# QuadV3.net
KiCad netlist of a schematic drawn in EasyEDA
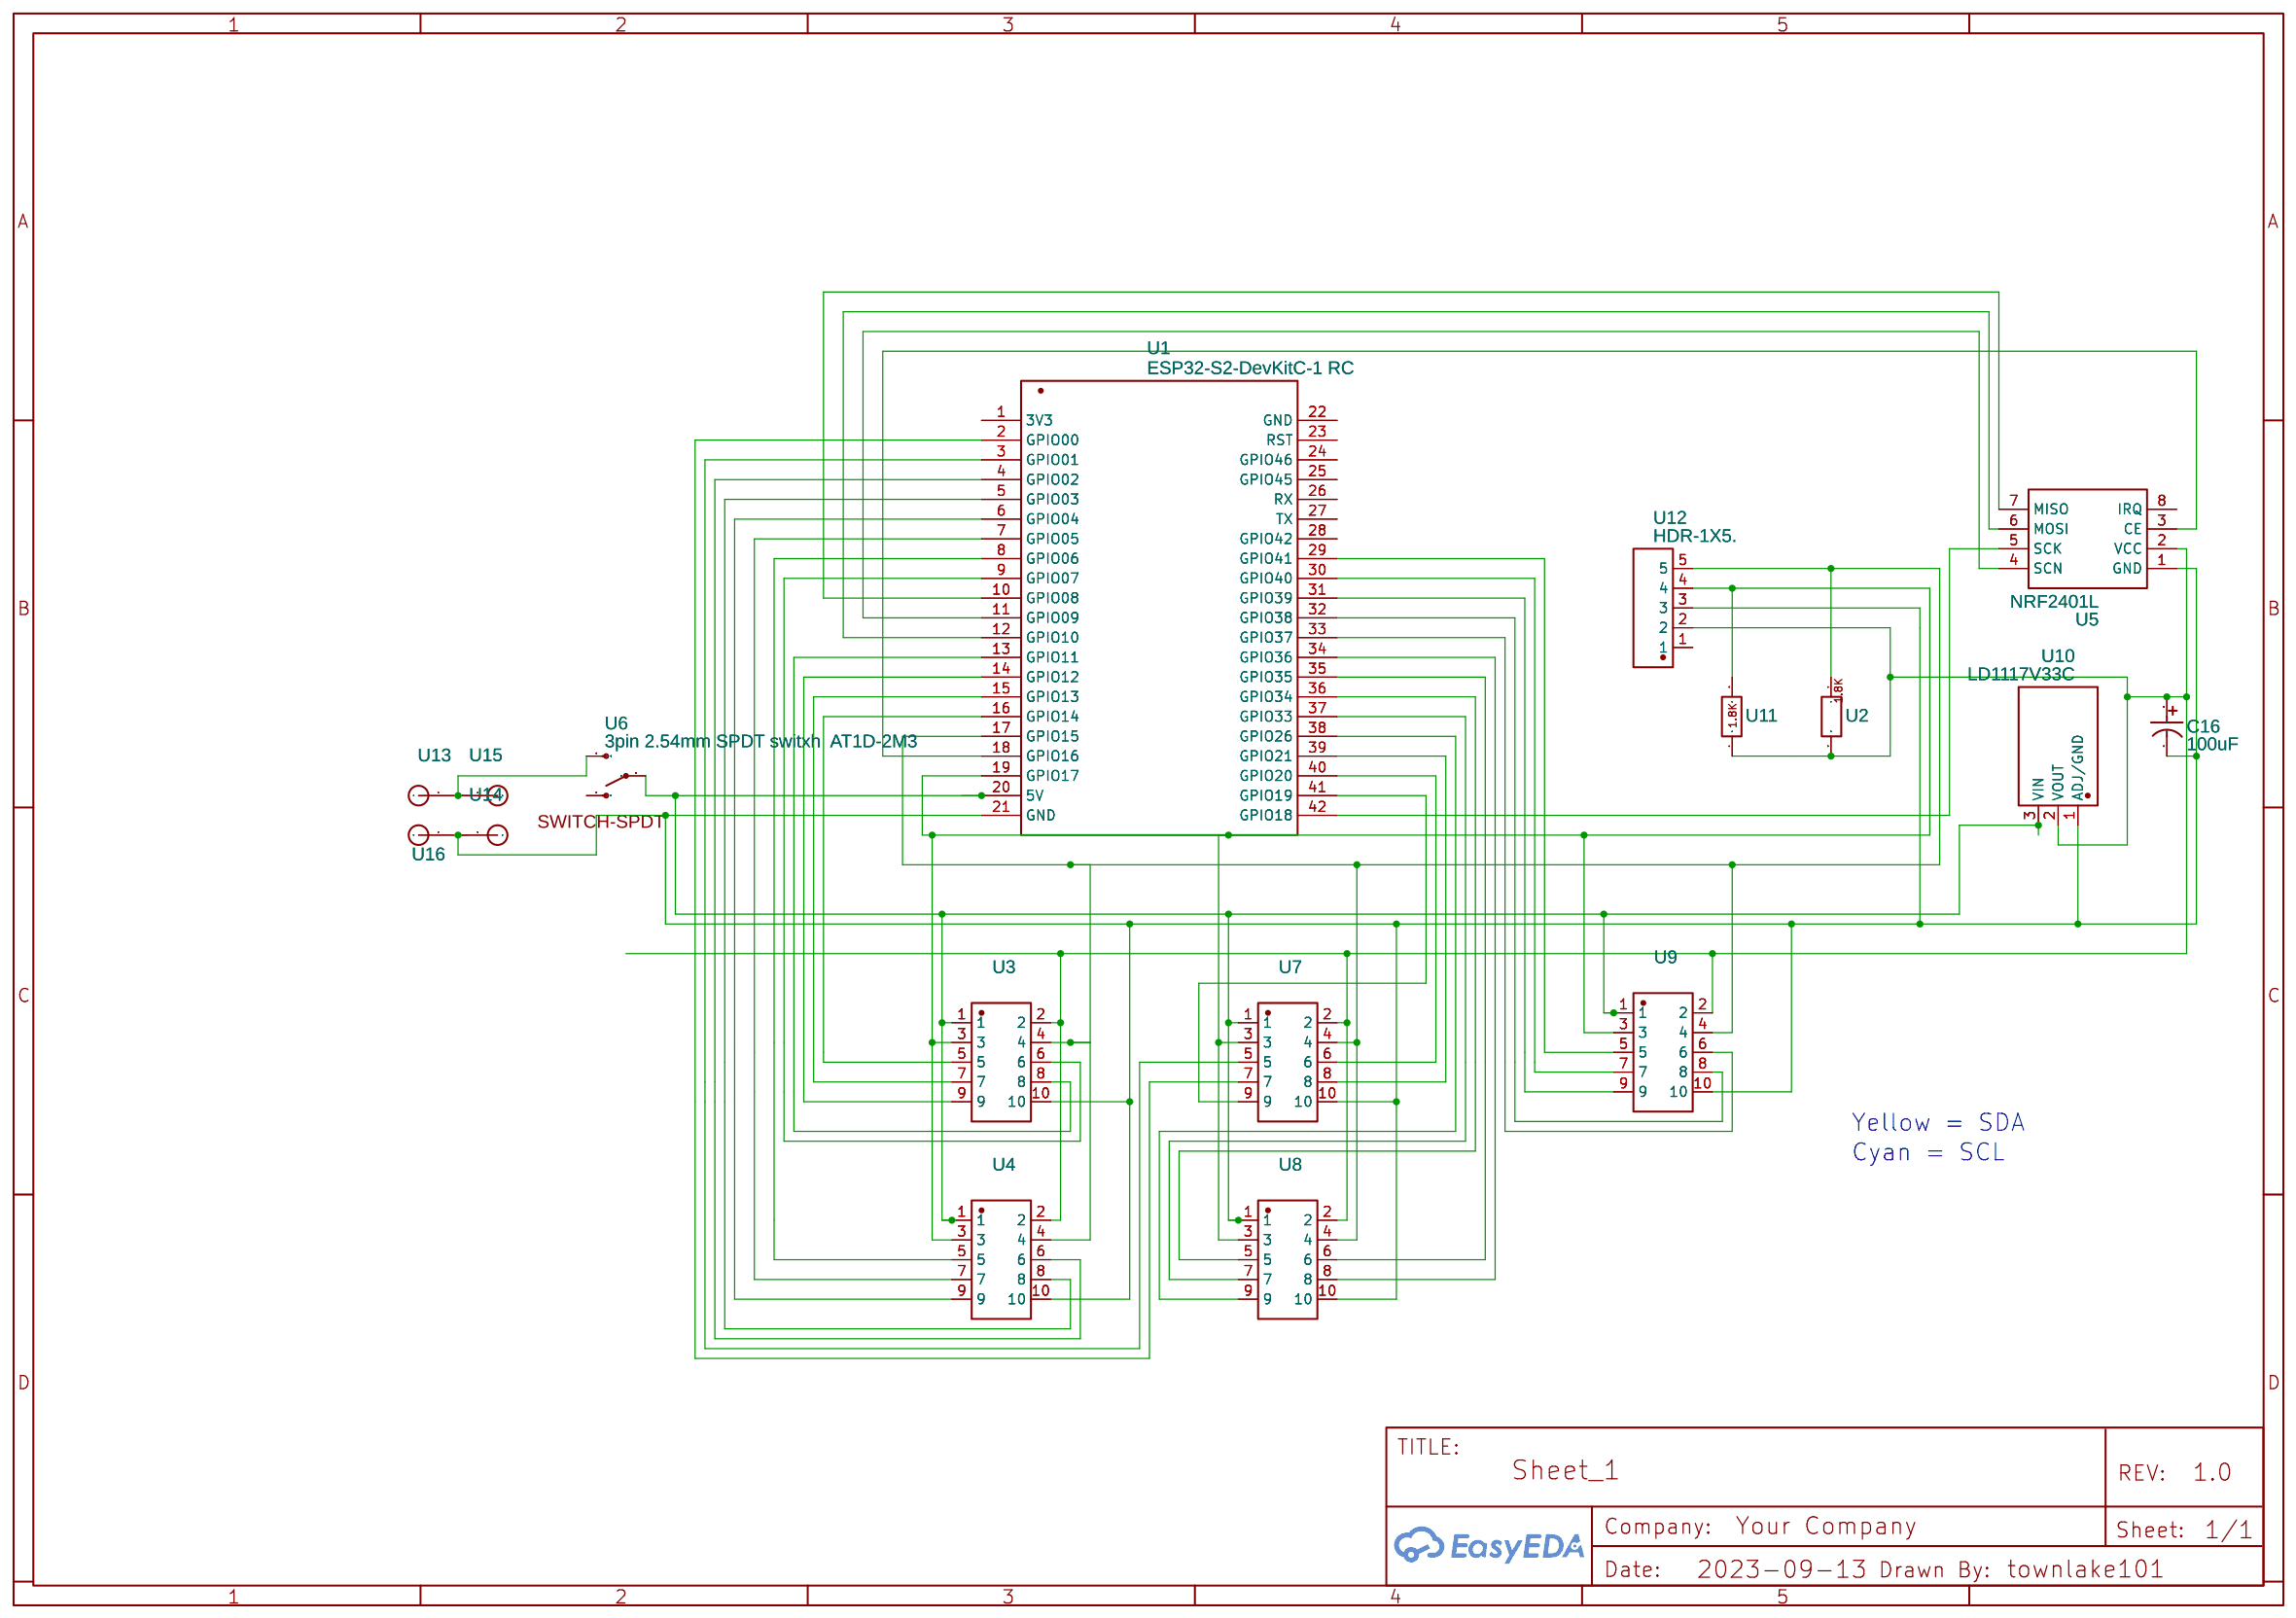
[diagram p0: schematic sheet]

(export (version "E")
  (design (tool "Eeschema 10.0.6"))
  (components
    (comp (ref "C16")
      (value "100uF")
      (fields (field (name "Manufacturer Part") "Jweo"))
      (libsource (lib "") (part "CAP-POL-1"))
    )
    (comp (ref "U1")
      (value "ESP32-S2-DevKitC-1 RC")
      (fields
        (field (name "Manufacturer Part") "ESP32-S2-DevKitC-1")
        (field (name "Manufacturer") "Espressif Manifacturer")
      )
      (libsource (lib "") (part "ESP32-S2-DevKitC-1 RC"))
    )
    (comp (ref "U2") (value "NO") (libsource (lib "") (part "1.8K_R_1/2W")))
    (comp (ref "U3")
      (value "NO")
      (fields
        (field (name "Manufacturer Part") "KH-2.54PH180-2X5P-L8.9")
        (field (name "Manufacturer") "kinghelm(金航标)")
      )
      (libsource (lib "") (part "KH-2.54PH180-2X5P"))
    )
    (comp (ref "U4")
      (value "NO")
      (fields
        (field (name "Manufacturer Part") "KH-2.54PH180-2X5P-L8.9")
        (field (name "Manufacturer") "kinghelm(金航标)")
      )
      (libsource (lib "") (part "KH-2.54PH180-2X5P"))
    )
    (comp (ref "U5")
      (value "NRF2401L")
      (fields (field (name "Manufacturer Part") "nrf2401l"))
      (libsource (lib "") (part "NRF2401L"))
    )
    (comp (ref "U6")
      (value "3pin 2.54mm SPDT switxh  AT1D-2M3")
      (libsource (lib "") (part "3pin 2.54mm SPDT switxh  AT1D-2M3"))
    )
    (comp (ref "U7")
      (value "NO")
      (fields
        (field (name "Manufacturer Part") "KH-2.54PH180-2X5P-L8.9")
        (field (name "Manufacturer") "kinghelm(金航标)")
      )
      (libsource (lib "") (part "KH-2.54PH180-2X5P"))
    )
    (comp (ref "U8")
      (value "NO")
      (fields
        (field (name "Manufacturer Part") "KH-2.54PH180-2X5P-L8.9")
        (field (name "Manufacturer") "kinghelm(金航标)")
      )
      (libsource (lib "") (part "KH-2.54PH180-2X5P"))
    )
    (comp (ref "U9")
      (value "NO")
      (fields
        (field (name "Manufacturer Part") "KH-2.54PH180-2X5P-L8.9")
        (field (name "Manufacturer") "kinghelm(金航标)")
      )
      (libsource (lib "") (part "KH-2.54PH180-2X5P"))
    )
    (comp (ref "U10")
      (value "LD1117V33C")
      (fields (field (name "Manufacturer") "ST(意法半导体)"))
      (libsource (lib "") (part "LD1117V33C"))
    )
    (comp (ref "U11") (value "NO") (libsource (lib "") (part "1.8K_R_1/2W_1")))
    (comp (ref "U12")
      (value "HDR-1X5.")
      (fields (field (name "Manufacturer Part") "HDR-1X5插件"))
      (libsource (lib "") (part "HDR-1X5."))
    )
    (comp (ref "U13")
      (value "NO")
      (fields (field (name "Manufacturer Part") "Wire Hole"))
      (libsource (lib "") (part "Wire Hole 14AWG"))
    )
    (comp (ref "U14")
      (value "NO")
      (fields (field (name "Manufacturer Part") "Wire Hole"))
      (libsource (lib "") (part "Wire Hole 14AWG_1"))
    )
    (comp (ref "U15")
      (value "NO")
      (fields (field (name "Manufacturer Part") "Wire Hole"))
      (libsource (lib "") (part "Wire Hole 14AWG_1"))
    )
    (comp (ref "U16")
      (value "NO")
      (fields (field (name "Manufacturer Part") "Wire Hole"))
      (libsource (lib "") (part "Wire Hole 14AWG"))
    )
  )
  (nets
    (net (code "1") (name "Net-(U1-5V)") (class "Default")
      (node (ref "U1") (pin "20") (pinfunction "5V_20") (pintype "bidirectional"))
      (node (ref "U10") (pin "3") (pinfunction "VIN_3") (pintype "unspecified"))
      (node (ref "U3") (pin "1") (pinfunction "1_1") (pintype "unspecified"))
      (node (ref "U4") (pin "1") (pinfunction "1_1") (pintype "unspecified"))
      (node (ref "U6") (pin "2") (pinfunction "P_2") (pintype "unspecified"))
      (node (ref "U7") (pin "1") (pinfunction "1_1") (pintype "unspecified"))
      (node (ref "U8") (pin "1") (pinfunction "1_1") (pintype "unspecified"))
      (node (ref "U9") (pin "1") (pinfunction "1_1") (pintype "unspecified"))
    )
    (net (code "2") (name "Net-(U1-GPIO00)") (class "Default")
      (node (ref "U1") (pin "2") (pinfunction "GPIO00_2") (pintype "passive"))
      (node (ref "U7") (pin "7") (pinfunction "7_7") (pintype "unspecified"))
    )
    (net (code "3") (name "Net-(U1-GPIO01)") (class "Default")
      (node (ref "U1") (pin "3") (pinfunction "GPIO01_3") (pintype "bidirectional"))
      (node (ref "U7") (pin "5") (pinfunction "5_5") (pintype "unspecified"))
    )
    (net (code "4") (name "Net-(U1-GPIO02)") (class "Default")
      (node (ref "U1") (pin "4") (pinfunction "GPIO02_4") (pintype "bidirectional"))
      (node (ref "U4") (pin "6") (pinfunction "6_6") (pintype "unspecified"))
    )
    (net (code "5") (name "Net-(U1-GPIO03)") (class "Default")
      (node (ref "U1") (pin "5") (pinfunction "GPIO03_5") (pintype "bidirectional"))
      (node (ref "U4") (pin "8") (pinfunction "8_8") (pintype "unspecified"))
    )
    (net (code "6") (name "Net-(U1-GPIO04)") (class "Default")
      (node (ref "U1") (pin "6") (pinfunction "GPIO04_6") (pintype "bidirectional"))
      (node (ref "U4") (pin "9") (pinfunction "9_9") (pintype "unspecified"))
    )
    (net (code "7") (name "Net-(U1-GPIO05)") (class "Default")
      (node (ref "U1") (pin "7") (pinfunction "GPIO05_7") (pintype "bidirectional"))
      (node (ref "U4") (pin "7") (pinfunction "7_7") (pintype "unspecified"))
    )
    (net (code "8") (name "Net-(U1-GPIO06)") (class "Default")
      (node (ref "U1") (pin "8") (pinfunction "GPIO06_8") (pintype "bidirectional"))
      (node (ref "U4") (pin "5") (pinfunction "5_5") (pintype "unspecified"))
    )
    (net (code "9") (name "Net-(U1-GPIO07)") (class "Default")
      (node (ref "U1") (pin "9") (pinfunction "GPIO07_9") (pintype "bidirectional"))
      (node (ref "U3") (pin "6") (pinfunction "6_6") (pintype "unspecified"))
    )
    (net (code "10") (name "Net-(U1-GPIO08)") (class "Default")
      (node (ref "U1") (pin "10") (pinfunction "GPIO08_10") (pintype "bidirectional"))
      (node (ref "U5") (pin "7") (pinfunction "MISO_7") (pintype "unspecified"))
    )
    (net (code "11") (name "Net-(U1-GPIO09)") (class "Default")
      (node (ref "U1") (pin "11") (pinfunction "GPIO09_11") (pintype "bidirectional"))
      (node (ref "U5") (pin "4") (pinfunction "SCN_4") (pintype "unspecified"))
    )
    (net (code "12") (name "Net-(U1-GPIO10)") (class "Default")
      (node (ref "U1") (pin "12") (pinfunction "GPIO10_12") (pintype "bidirectional"))
      (node (ref "U5") (pin "6") (pinfunction "MOSI_6") (pintype "unspecified"))
    )
    (net (code "13") (name "Net-(U1-GPIO11)") (class "Default")
      (node (ref "U1") (pin "13") (pinfunction "GPIO11_13") (pintype "bidirectional"))
      (node (ref "U3") (pin "8") (pinfunction "8_8") (pintype "unspecified"))
    )
    (net (code "14") (name "Net-(U1-GPIO12)") (class "Default")
      (node (ref "U1") (pin "14") (pinfunction "GPIO12_14") (pintype "bidirectional"))
      (node (ref "U3") (pin "9") (pinfunction "9_9") (pintype "unspecified"))
    )
    (net (code "15") (name "Net-(U1-GPIO13)") (class "Default")
      (node (ref "U1") (pin "15") (pinfunction "GPIO13_15") (pintype "bidirectional"))
      (node (ref "U3") (pin "7") (pinfunction "7_7") (pintype "unspecified"))
    )
    (net (code "16") (name "Net-(U1-GPIO14)") (class "Default")
      (node (ref "U1") (pin "16") (pinfunction "GPIO14_16") (pintype "bidirectional"))
      (node (ref "U3") (pin "5") (pinfunction "5_5") (pintype "unspecified"))
    )
    (net (code "17") (name "Net-(U1-GPIO15)") (class "Default")
      (node (ref "U1") (pin "17") (pinfunction "GPIO15_17") (pintype "bidirectional"))
      (node (ref "U12") (pin "5") (pinfunction "5_5") (pintype "unspecified"))
      (node (ref "U2") (pin "1") (pinfunction "1_1") (pintype "unspecified"))
      (node (ref "U3") (pin "4") (pinfunction "4_4") (pintype "unspecified"))
      (node (ref "U4") (pin "4") (pinfunction "4_4") (pintype "unspecified"))
      (node (ref "U7") (pin "4") (pinfunction "4_4") (pintype "unspecified"))
      (node (ref "U8") (pin "4") (pinfunction "4_4") (pintype "unspecified"))
      (node (ref "U9") (pin "4") (pinfunction "4_4") (pintype "unspecified"))
    )
    (net (code "18") (name "Net-(U1-GPIO16)") (class "Default")
      (node (ref "U1") (pin "18") (pinfunction "GPIO16_18") (pintype "bidirectional"))
      (node (ref "U5") (pin "3") (pinfunction "CE_3") (pintype "unspecified"))
    )
    (net (code "19") (name "Net-(U1-GPIO17)") (class "Default")
      (node (ref "U1") (pin "19") (pinfunction "GPIO17_19") (pintype "bidirectional"))
      (node (ref "U11") (pin "2") (pinfunction "2_2") (pintype "unspecified"))
      (node (ref "U12") (pin "4") (pinfunction "4_4") (pintype "unspecified"))
      (node (ref "U3") (pin "3") (pinfunction "3_3") (pintype "unspecified"))
      (node (ref "U4") (pin "3") (pinfunction "3_3") (pintype "unspecified"))
      (node (ref "U7") (pin "3") (pinfunction "3_3") (pintype "unspecified"))
      (node (ref "U8") (pin "3") (pinfunction "3_3") (pintype "unspecified"))
      (node (ref "U9") (pin "3") (pinfunction "3_3") (pintype "unspecified"))
    )
    (net (code "20") (name "Net-(U1-GPIO18)") (class "Default")
      (node (ref "U1") (pin "42") (pinfunction "GPIO18_42") (pintype "passive"))
      (node (ref "U5") (pin "5") (pinfunction "SCK_5") (pintype "unspecified"))
    )
    (net (code "21") (name "Net-(U1-GPIO19)") (class "Default")
      (node (ref "U1") (pin "41") (pinfunction "GPIO19_41") (pintype "bidirectional"))
      (node (ref "U7") (pin "9") (pinfunction "9_9") (pintype "unspecified"))
    )
    (net (code "22") (name "Net-(U1-GPIO20)") (class "Default")
      (node (ref "U1") (pin "40") (pinfunction "GPIO20_40") (pintype "bidirectional"))
      (node (ref "U7") (pin "6") (pinfunction "6_6") (pintype "unspecified"))
    )
    (net (code "23") (name "Net-(U1-GPIO21)") (class "Default")
      (node (ref "U1") (pin "39") (pinfunction "GPIO21_39") (pintype "bidirectional"))
      (node (ref "U7") (pin "8") (pinfunction "8_8") (pintype "unspecified"))
    )
    (net (code "24") (name "Net-(U1-GPIO26)") (class "Default")
      (node (ref "U1") (pin "38") (pinfunction "GPIO26_38") (pintype "bidirectional"))
      (node (ref "U8") (pin "9") (pinfunction "9_9") (pintype "unspecified"))
    )
    (net (code "25") (name "Net-(U1-GPIO33)") (class "Default")
      (node (ref "U1") (pin "37") (pinfunction "GPIO33_37") (pintype "bidirectional"))
      (node (ref "U8") (pin "7") (pinfunction "7_7") (pintype "unspecified"))
    )
    (net (code "26") (name "Net-(U1-GPIO34)") (class "Default")
      (node (ref "U1") (pin "36") (pinfunction "GPIO34_36") (pintype "input"))
      (node (ref "U8") (pin "5") (pinfunction "5_5") (pintype "unspecified"))
    )
    (net (code "27") (name "Net-(U1-GPIO35)") (class "Default")
      (node (ref "U1") (pin "35") (pinfunction "GPIO35_35") (pintype "bidirectional"))
      (node (ref "U8") (pin "6") (pinfunction "6_6") (pintype "unspecified"))
    )
    (net (code "28") (name "Net-(U1-GPIO36)") (class "Default")
      (node (ref "U1") (pin "34") (pinfunction "GPIO36_34") (pintype "bidirectional"))
      (node (ref "U8") (pin "8") (pinfunction "8_8") (pintype "unspecified"))
    )
    (net (code "29") (name "Net-(U1-GPIO37)") (class "Default")
      (node (ref "U1") (pin "33") (pinfunction "GPIO37_33") (pintype "bidirectional"))
      (node (ref "U9") (pin "6") (pinfunction "6_6") (pintype "unspecified"))
    )
    (net (code "30") (name "Net-(U1-GPIO38)") (class "Default")
      (node (ref "U1") (pin "32") (pinfunction "GPIO38_32") (pintype "bidirectional"))
      (node (ref "U9") (pin "8") (pinfunction "8_8") (pintype "unspecified"))
    )
    (net (code "31") (name "Net-(U1-GPIO39)") (class "Default")
      (node (ref "U1") (pin "31") (pinfunction "GPIO39_31") (pintype "bidirectional"))
      (node (ref "U9") (pin "9") (pinfunction "9_9") (pintype "unspecified"))
    )
    (net (code "32") (name "Net-(U1-GPIO40)") (class "Default")
      (node (ref "U1") (pin "30") (pinfunction "GPIO40_30") (pintype "bidirectional"))
      (node (ref "U9") (pin "7") (pinfunction "7_7") (pintype "unspecified"))
    )
    (net (code "33") (name "Net-(U1-GPIO41)") (class "Default")
      (node (ref "U1") (pin "29") (pinfunction "GPIO41_29") (pintype "bidirectional"))
      (node (ref "U9") (pin "5") (pinfunction "5_5") (pintype "unspecified"))
    )
    (net (code "34") (name "Net-(U6-S)") (class "Default")
      (node (ref "U13") (pin "1") (pinfunction "1_1") (pintype "unspecified"))
      (node (ref "U15") (pin "1") (pinfunction "1_1") (pintype "unspecified"))
      (node (ref "U6") (pin "3") (pinfunction "S_3") (pintype "unspecified"))
    )
    (net (code "35") (name "Net-(U10-ADJ{slash}GND)") (class "Default")
      (node (ref "C16") (pin "2") (pinfunction "2_2") (pintype "input"))
      (node (ref "U1") (pin "21") (pinfunction "GND_21") (pintype "passive"))
      (node (ref "U10") (pin "1") (pinfunction "ADJ/GND_1") (pintype "unspecified"))
      (node (ref "U12") (pin "3") (pinfunction "3_3") (pintype "unspecified"))
      (node (ref "U14") (pin "1") (pinfunction "1_1") (pintype "unspecified"))
      (node (ref "U16") (pin "1") (pinfunction "1_1") (pintype "unspecified"))
      (node (ref "U3") (pin "10") (pinfunction "10_10") (pintype "unspecified"))
      (node (ref "U4") (pin "10") (pinfunction "10_10") (pintype "unspecified"))
      (node (ref "U5") (pin "1") (pinfunction "GND_1") (pintype "unspecified"))
      (node (ref "U7") (pin "10") (pinfunction "10_10") (pintype "unspecified"))
      (node (ref "U8") (pin "10") (pinfunction "10_10") (pintype "unspecified"))
      (node (ref "U9") (pin "10") (pinfunction "10_10") (pintype "unspecified"))
    )
    (net (code "36") (name "Net-(U10-VOUT)") (class "Default")
      (node (ref "C16") (pin "1") (pinfunction "1_1") (pintype "input"))
      (node (ref "U10") (pin "2") (pinfunction "VOUT_2") (pintype "unspecified"))
      (node (ref "U11") (pin "1") (pinfunction "1_1") (pintype "unspecified"))
      (node (ref "U12") (pin "2") (pinfunction "2_2") (pintype "unspecified"))
      (node (ref "U2") (pin "2") (pinfunction "2_2") (pintype "unspecified"))
      (node (ref "U3") (pin "2") (pinfunction "2_2") (pintype "unspecified"))
      (node (ref "U4") (pin "2") (pinfunction "2_2") (pintype "unspecified"))
      (node (ref "U5") (pin "2") (pinfunction "VCC_2") (pintype "unspecified"))
      (node (ref "U7") (pin "2") (pinfunction "2_2") (pintype "unspecified"))
      (node (ref "U8") (pin "2") (pinfunction "2_2") (pintype "unspecified"))
      (node (ref "U9") (pin "2") (pinfunction "2_2") (pintype "unspecified"))
    )
    (net (code "37") (name "unconnected-(U1-3V3-Pad1)") (class "Default")
      (node (ref "U1") (pin "1") (pinfunction "3V3_1") (pintype "passive"))
    )
    (net (code "38") (name "unconnected-(U1-GND-Pad22)") (class "Default")
      (node (ref "U1") (pin "22") (pinfunction "GND_22") (pintype "passive"))
    )
    (net (code "39") (name "unconnected-(U1-GPIO42-Pad28)") (class "Default")
      (node (ref "U1") (pin "28") (pinfunction "GPIO42_28") (pintype "bidirectional"))
    )
    (net (code "40") (name "unconnected-(U1-GPIO45-Pad25)") (class "Default")
      (node (ref "U1") (pin "25") (pinfunction "GPIO45_25") (pintype "bidirectional"))
    )
    (net (code "41") (name "unconnected-(U1-GPIO46-Pad24)") (class "Default")
      (node (ref "U1") (pin "24") (pinfunction "GPIO46_24") (pintype "bidirectional"))
    )
    (net (code "42") (name "unconnected-(U1-RST-Pad23)") (class "Default")
      (node (ref "U1") (pin "23") (pinfunction "RST_23") (pintype "bidirectional"))
    )
    (net (code "43") (name "unconnected-(U1-RX-Pad26)") (class "Default")
      (node (ref "U1") (pin "26") (pinfunction "RX_26") (pintype "bidirectional"))
    )
    (net (code "44") (name "unconnected-(U1-TX-Pad27)") (class "Default")
      (node (ref "U1") (pin "27") (pinfunction "TX_27") (pintype "bidirectional"))
    )
    (net (code "45") (name "unconnected-(U5-IRQ-Pad8)") (class "Default")
      (node (ref "U5") (pin "8") (pinfunction "IRQ_8") (pintype "unspecified"))
    )
    (net (code "46") (name "unconnected-(U6-O-Pad1)") (class "Default")
      (node (ref "U6") (pin "1") (pinfunction "O_1") (pintype "unspecified"))
    )
    (net (code "47") (name "unconnected-(U12-Pad1)") (class "Default")
      (node (ref "U12") (pin "1") (pinfunction "1_1") (pintype "unspecified"))
    )
  )
)
